# sheet.net
KiCad netlist of a schematic drawn in Altium Designer
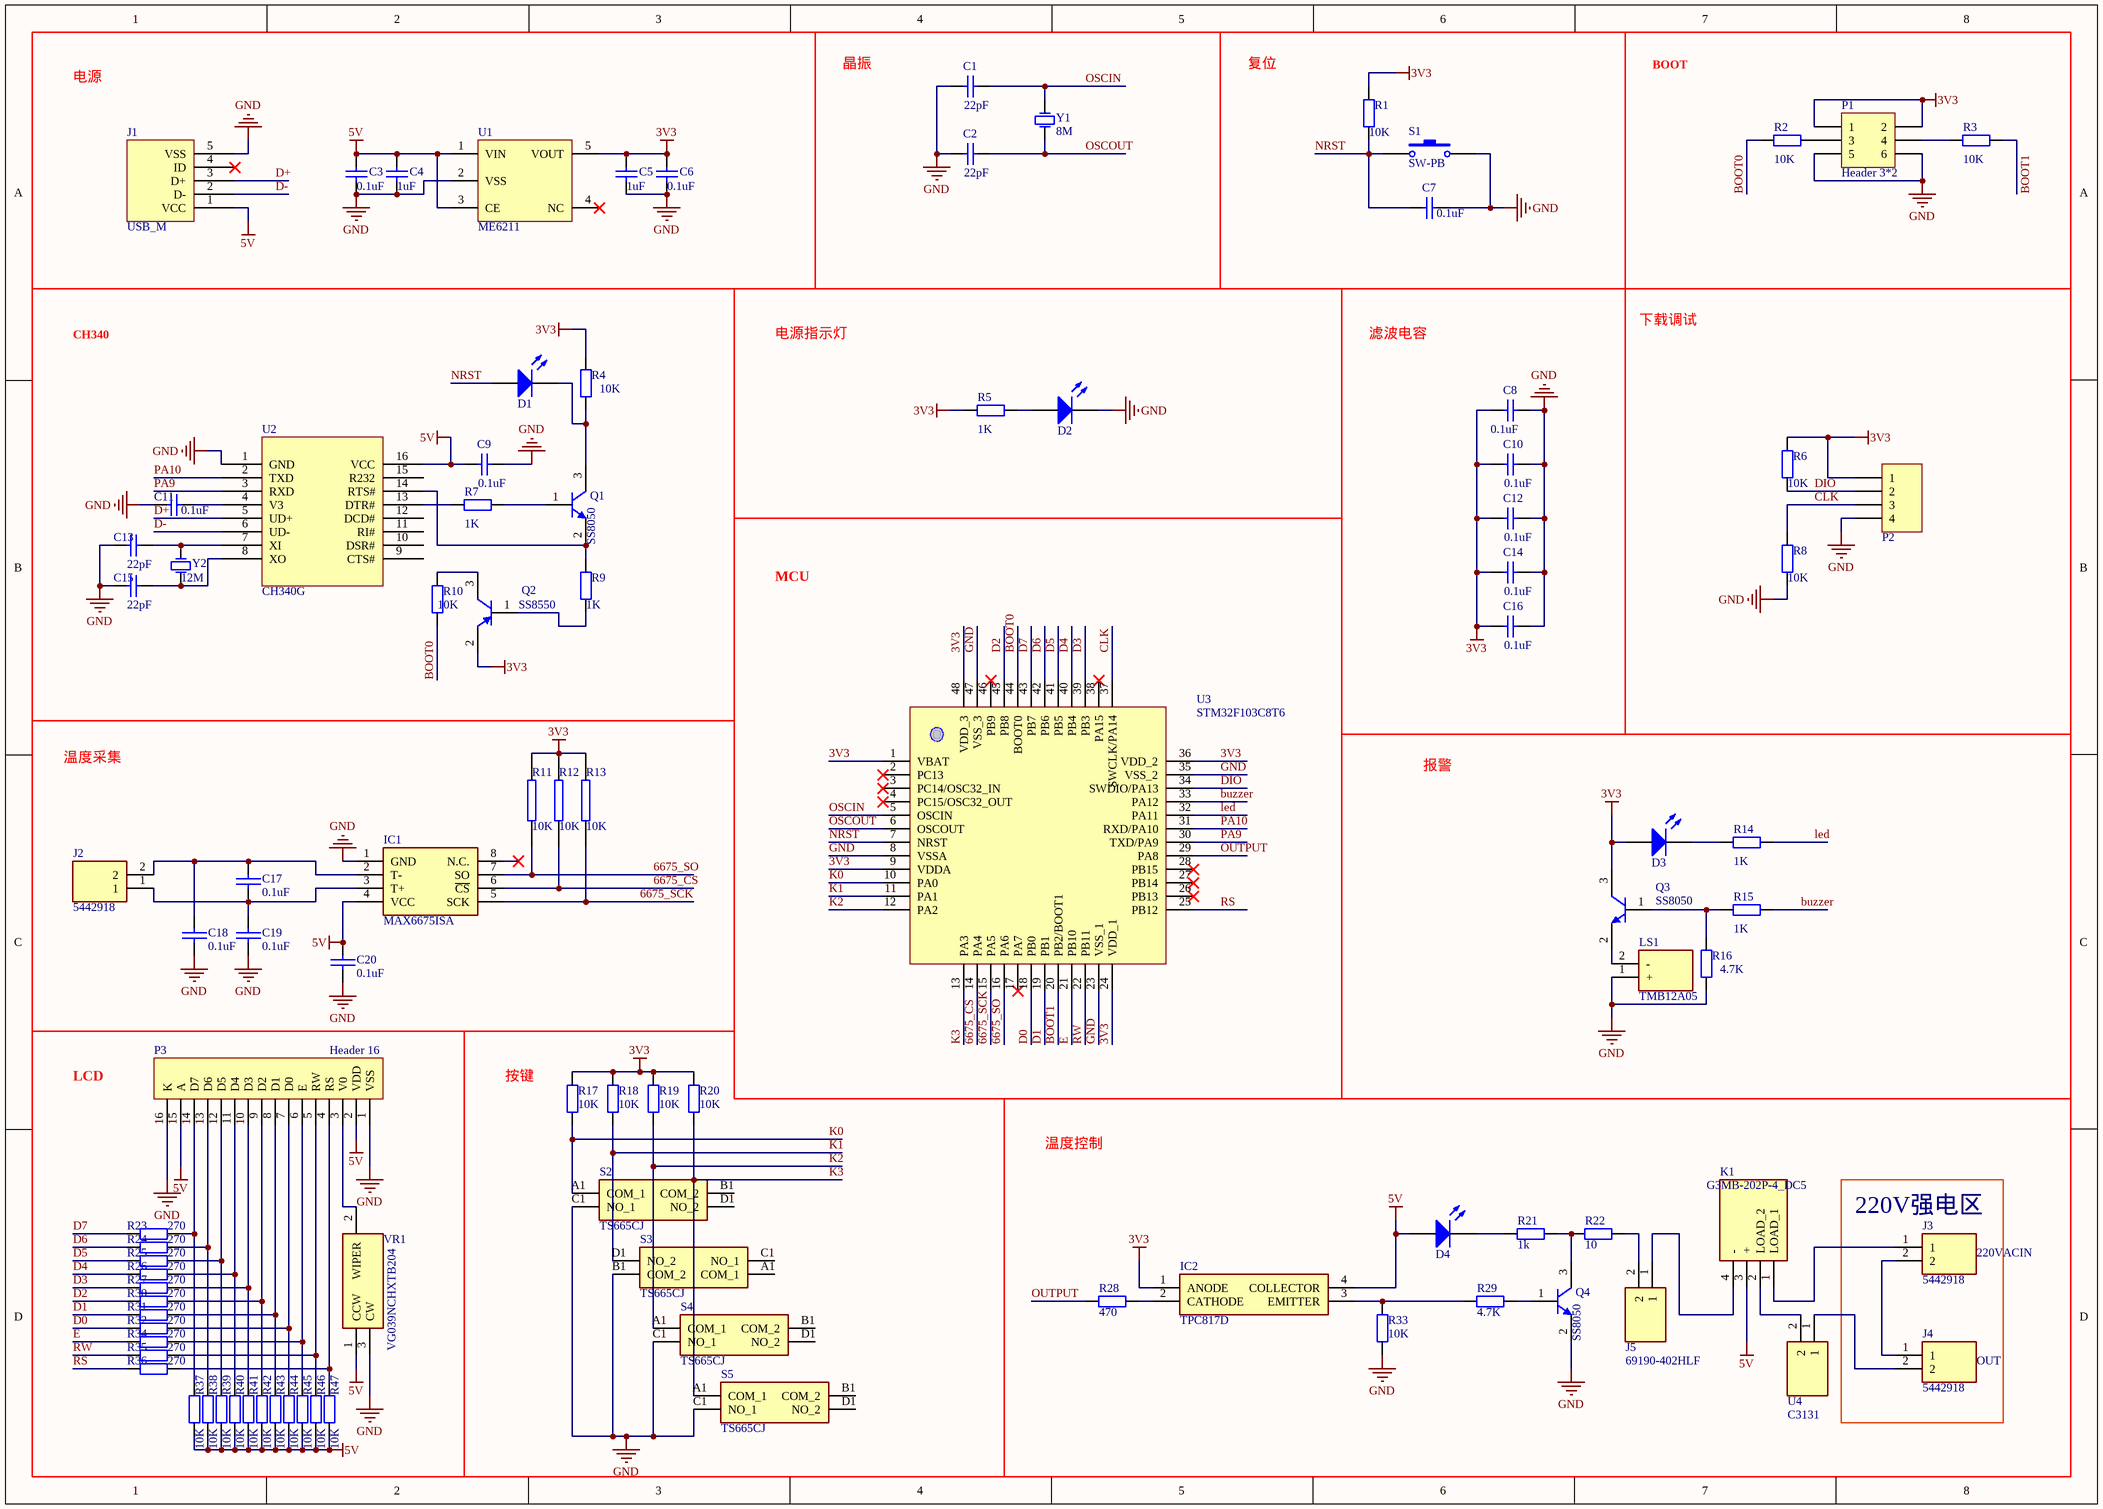
[diagram p0: sheet.SchDoc]

(export (version "E")
  (design (tool "Eeschema 10.0.6"))
  (components
    (comp (ref "C1")
      (value "22pF")
      (footprint "0603_C")
      (description "无极性电容")
      (fields (field (name "PUBLISHER") "Altium Limited"))
      (libsource (lib "stm32test") (part "Cap"))
    )
    (comp (ref "C2")
      (value "22pF")
      (footprint "0603_C")
      (description "无极性电容")
      (fields (field (name "PUBLISHER") "Altium Limited"))
      (libsource (lib "stm32test") (part "Cap"))
    )
    (comp (ref "C3")
      (value "0.1uF")
      (footprint "0603_C")
      (description "无极性电容")
      (fields (field (name "PUBLISHER") "Altium Limited"))
      (libsource (lib "stm32test") (part "Cap"))
    )
    (comp (ref "C4")
      (value "1uF")
      (footprint "0603_C")
      (description "无极性电容")
      (fields (field (name "PUBLISHER") "Altium Limited"))
      (libsource (lib "stm32test") (part "Cap"))
    )
    (comp (ref "C5")
      (value "1uF")
      (footprint "0603_C")
      (description "无极性电容")
      (fields (field (name "PUBLISHER") "Altium Limited"))
      (libsource (lib "stm32test") (part "Cap"))
    )
    (comp (ref "C6")
      (value "0.1uF")
      (footprint "0603_C")
      (description "无极性电容")
      (fields (field (name "PUBLISHER") "Altium Limited"))
      (libsource (lib "stm32test") (part "Cap"))
    )
    (comp (ref "C7")
      (value "0.1uF")
      (footprint "0603_C")
      (description "无极性电容")
      (fields (field (name "PUBLISHER") "Altium Limited"))
      (libsource (lib "stm32test") (part "Cap"))
    )
    (comp (ref "C8")
      (value "0.1uF")
      (footprint "0603_C")
      (description "无极性电容")
      (fields (field (name "PUBLISHER") "Altium Limited"))
      (libsource (lib "stm32test") (part "Cap"))
    )
    (comp (ref "C9")
      (value "0.1uF")
      (footprint "0603_C")
      (description "无极性电容")
      (fields (field (name "PUBLISHER") "Altium Limited"))
      (libsource (lib "stm32test") (part "Cap"))
    )
    (comp (ref "C10")
      (value "0.1uF")
      (footprint "0603_C")
      (description "无极性电容")
      (fields (field (name "PUBLISHER") "Altium Limited"))
      (libsource (lib "stm32test") (part "Cap"))
    )
    (comp (ref "C11")
      (value "0.1uF")
      (footprint "0603_C")
      (description "无极性电容")
      (fields (field (name "PUBLISHER") "Altium Limited"))
      (libsource (lib "stm32test") (part "Cap"))
    )
    (comp (ref "C12")
      (value "0.1uF")
      (footprint "0603_C")
      (description "无极性电容")
      (fields (field (name "PUBLISHER") "Altium Limited"))
      (libsource (lib "stm32test") (part "Cap"))
    )
    (comp (ref "C13")
      (value "22pF")
      (footprint "0603_C")
      (description "无极性电容")
      (fields (field (name "PUBLISHER") "Altium Limited"))
      (libsource (lib "stm32test") (part "Cap"))
    )
    (comp (ref "C14")
      (value "0.1uF")
      (footprint "0603_C")
      (description "无极性电容")
      (fields (field (name "PUBLISHER") "Altium Limited"))
      (libsource (lib "stm32test") (part "Cap"))
    )
    (comp (ref "C15")
      (value "22pF")
      (footprint "0603_C")
      (description "无极性电容")
      (fields (field (name "PUBLISHER") "Altium Limited"))
      (libsource (lib "stm32test") (part "Cap"))
    )
    (comp (ref "C16")
      (value "0.1uF")
      (footprint "0603_C")
      (description "无极性电容")
      (fields (field (name "PUBLISHER") "Altium Limited"))
      (libsource (lib "stm32test") (part "Cap"))
    )
    (comp (ref "C17")
      (value "0.1uF")
      (footprint "1206")
      (description "Capacitor")
      (libsource (lib "电容") (part "普通电容"))
    )
    (comp (ref "C18")
      (value "0.1uF")
      (footprint "1206")
      (description "Capacitor")
      (libsource (lib "电容") (part "普通电容"))
    )
    (comp (ref "C19")
      (value "0.1uF")
      (footprint "1206")
      (description "Capacitor")
      (libsource (lib "电容") (part "普通电容"))
    )
    (comp (ref "C20")
      (value "0.1uF")
      (footprint "1206")
      (description "Capacitor")
      (libsource (lib "电容") (part "普通电容"))
    )
    (comp (ref "D1")
      (value "LED0")
      (footprint "LED_0805_Blue")
      (description "发光二极管")
      (fields (field (name "PUBLISHER") "Altium Limited"))
      (libsource (lib "stm32test") (part "LED0"))
    )
    (comp (ref "D2")
      (value "LED0")
      (footprint "LED_0805_Blue")
      (description "发光二极管")
      (fields (field (name "PUBLISHER") "Altium Limited"))
      (libsource (lib "stm32test") (part "LED0"))
    )
    (comp (ref "D3")
      (value "LED0")
      (footprint "LED_0805_Blue")
      (description "发光二极管")
      (fields (field (name "PUBLISHER") "Altium Limited"))
      (libsource (lib "stm32test") (part "LED0"))
    )
    (comp (ref "D4")
      (value "LED0")
      (footprint "LED_0805_Blue")
      (description "发光二极管")
      (fields (field (name "PUBLISHER") "Altium Limited"))
      (libsource (lib "stm32test") (part "LED0"))
    )
    (comp (ref "IC1")
      (value "MAX6675ISA")
      (footprint "SamacSys:SOIC127P600X175-8N")
      (description "Integrated Circuit")
      (libsource (lib "SamacSys") (part "MAX6675ISA"))
    )
    (comp (ref "IC2")
      (value "TPC817D")
      (footprint "SamacSys:DIP810W50P254L460H368Q4N")
      (description "Integrated Circuit")
      (fields (field (name "MOUSER PART NUMBER") "821-TPC817D"))
      (libsource (lib "SamacSys") (part "TPC817D"))
    )
    (comp (ref "J1")
      (value "USB_M")
      (footprint "USB")
      (description "MicroUSB接口")
      (libsource (lib "stm32test") (part "USB_M"))
    )
    (comp (ref "J2")
      (value "5442918")
      (footprint "SamacSys:SHDR2W100P0X508_1X2_1016X1120X1820P")
      (description "Connector")
      (fields (field (name "MOUSER PART NUMBER") "651-5442918"))
      (libsource (lib "") (part "5442918_1"))
    )
    (comp (ref "J3")
      (value "5442918")
      (footprint "SamacSys:SHDR2W100P0X508_1X2_1016X1120X1820P")
      (description "Connector")
      (fields (field (name "MOUSER PART NUMBER") "651-5442918"))
      (libsource (lib "*") (part "5442918"))
    )
    (comp (ref "J4")
      (value "5442918")
      (footprint "SamacSys:SHDR2W100P0X508_1X2_1016X1120X1820P")
      (description "Connector")
      (fields (field (name "MOUSER PART NUMBER") "651-5442918"))
      (libsource (lib "*") (part "5442918"))
    )
    (comp (ref "J5")
      (value "69190-402HLF")
      (footprint "SamacSys:HDRV2W90P0X254_1X2_508X241X858P")
      (description "Connector")
      (fields
        (field (name "MOUSER PART NUMBER") "649-69190-402HLF")
        (field (name "RS PART NUMBER") "8632731")
      )
      (libsource (lib "*") (part "69190-402HLF"))
    )
    (comp (ref "K1")
      (value "G3MB-202P-4_DC5")
      (footprint "SamacSys:G3MB202P4DC5")
      (description "Relay or Contactor")
      (fields
        (field (name "MANUFACTURER_PART_NUMBER") "G3MB-202P-4 DC5")
        (field (name "MOUSER PART NUMBER") "653-G3MB-202P4DC5")
      )
      (libsource (lib "*") (part "G3MB-202P-4_DC5"))
    )
    (comp (ref "LS1")
      (value "TMB12A05")
      (footprint "SamacSys:TMB12A05")
      (description "Loudspeaker or Buzzer")
      (libsource (lib "*") (part "TMB12A05"))
    )
    (comp (ref "P1")
      (value "Header 3*2")
      (footprint "HDR3X2")
      (description "接插件")
      (libsource (lib "stm32test") (part "Header 3*2"))
    )
    (comp (ref "P2")
      (value "Header 4")
      (footprint "HDR4X1_A")
      (description "接插件")
      (fields (field (name "PUBLISHER") "Altium Limited"))
      (libsource (lib "stm32test") (part "Header 4"))
    )
    (comp (ref "P3")
      (value "Header 16")
      (footprint "HDR16X1_A")
      (description "Header16贴片")
      (fields (field (name "PUBLISHER") "Altium Limited"))
      (libsource (lib "stm32test") (part "Header 16"))
    )
    (comp (ref "Q1")
      (value "SS8050")
      (footprint "SOT-23")
      (description "NPN贴片三极管")
      (fields (field (name "PUBLISHER") "Altium Limited"))
      (libsource (lib "stm32test") (part "SS8050"))
    )
    (comp (ref "Q2")
      (value "SS8550")
      (footprint "SOT-23")
      (description "PNP贴片三极管")
      (fields (field (name "PUBLISHER") "Altium Limited"))
      (libsource (lib "stm32test") (part "SS8550"))
    )
    (comp (ref "Q3")
      (value "SS8050")
      (footprint "SOT-23")
      (description "NPN贴片三极管")
      (fields (field (name "PUBLISHER") "Altium Limited"))
      (libsource (lib "stm32test") (part "SS8050"))
    )
    (comp (ref "Q4")
      (value "SS8050")
      (footprint "SOT-23")
      (description "NPN贴片三极管")
      (fields (field (name "PUBLISHER") "Altium Limited"))
      (libsource (lib "stm32test") (part "SS8050"))
    )
    (comp (ref "R1")
      (value "10K")
      (footprint "0603_R")
      (description "贴片电阻")
      (fields (field (name "PUBLISHER") "Altium Limited"))
      (libsource (lib "stm32test") (part "Res1"))
    )
    (comp (ref "R2")
      (value "10K")
      (footprint "0603_R")
      (description "贴片电阻")
      (fields (field (name "PUBLISHER") "Altium Limited"))
      (libsource (lib "") (part "Res1_2"))
    )
    (comp (ref "R3")
      (value "10K")
      (footprint "0603_R")
      (description "贴片电阻")
      (fields (field (name "PUBLISHER") "Altium Limited"))
      (libsource (lib "") (part "Res1_2"))
    )
    (comp (ref "R4")
      (value "10K")
      (footprint "0603_R")
      (description "贴片电阻")
      (fields (field (name "PUBLISHER") "Altium Limited"))
      (libsource (lib "stm32test") (part "Res1"))
    )
    (comp (ref "R5")
      (value "1K")
      (footprint "0603_R")
      (description "贴片电阻")
      (fields (field (name "PUBLISHER") "Altium Limited"))
      (libsource (lib "") (part "Res1_2"))
    )
    (comp (ref "R6")
      (value "10K")
      (footprint "0603_R")
      (description "贴片电阻")
      (fields (field (name "PUBLISHER") "Altium Limited"))
      (libsource (lib "stm32test") (part "Res1"))
    )
    (comp (ref "R7")
      (value "1K")
      (footprint "0603_R")
      (description "贴片电阻")
      (fields (field (name "PUBLISHER") "Altium Limited"))
      (libsource (lib "") (part "Res1_2"))
    )
    (comp (ref "R8")
      (value "10K")
      (footprint "0603_R")
      (description "贴片电阻")
      (fields (field (name "PUBLISHER") "Altium Limited"))
      (libsource (lib "stm32test") (part "Res1"))
    )
    (comp (ref "R9")
      (value "1K")
      (footprint "0603_R")
      (description "贴片电阻")
      (fields (field (name "PUBLISHER") "Altium Limited"))
      (libsource (lib "stm32test") (part "Res1"))
    )
    (comp (ref "R10")
      (value "10K")
      (footprint "0603_R")
      (description "贴片电阻")
      (fields (field (name "PUBLISHER") "Altium Limited"))
      (libsource (lib "stm32test") (part "Res1"))
    )
    (comp (ref "R11") (value "10K") (footprint "1206") (libsource (lib "*") (part "RES2")))
    (comp (ref "R12") (value "10K") (footprint "1206") (libsource (lib "*") (part "RES2")))
    (comp (ref "R13") (value "10K") (footprint "1206") (libsource (lib "*") (part "RES2")))
    (comp (ref "R14")
      (value "1K")
      (footprint "0603_R")
      (description "贴片电阻")
      (fields (field (name "PUBLISHER") "Altium Limited"))
      (libsource (lib "") (part "Res1_2"))
    )
    (comp (ref "R15")
      (value "1K")
      (footprint "0603_R")
      (description "贴片电阻")
      (fields (field (name "PUBLISHER") "Altium Limited"))
      (libsource (lib "") (part "Res1_2"))
    )
    (comp (ref "R16")
      (value "4.7K")
      (footprint "0603_R")
      (description "贴片电阻")
      (fields (field (name "PUBLISHER") "Altium Limited"))
      (libsource (lib "stm32test") (part "Res1"))
    )
    (comp (ref "R17")
      (value "10K")
      (footprint "1206")
      (description "Resistor")
      (fields (field (name "PUBLISHER") "Altium Limited"))
      (libsource (lib "") (part "Res2_1"))
    )
    (comp (ref "R18")
      (value "10K")
      (footprint "1206")
      (description "Resistor")
      (fields (field (name "PUBLISHER") "Altium Limited"))
      (libsource (lib "") (part "Res2_1"))
    )
    (comp (ref "R19")
      (value "10K")
      (footprint "1206")
      (description "Resistor")
      (fields (field (name "PUBLISHER") "Altium Limited"))
      (libsource (lib "") (part "Res2_1"))
    )
    (comp (ref "R20")
      (value "10K")
      (footprint "1206")
      (description "Resistor")
      (fields (field (name "PUBLISHER") "Altium Limited"))
      (libsource (lib "") (part "Res2_1"))
    )
    (comp (ref "R21")
      (value "1k")
      (footprint "1206")
      (description "Resistor")
      (fields (field (name "PUBLISHER") "Altium Limited"))
      (libsource (lib "Miscellaneous Devices") (part "Res2"))
    )
    (comp (ref "R22")
      (value "10")
      (footprint "1206")
      (description "Resistor")
      (fields (field (name "PUBLISHER") "Altium Limited"))
      (libsource (lib "Miscellaneous Devices") (part "Res2"))
    )
    (comp (ref "R23")
      (value "270")
      (footprint "0603_R")
      (description "贴片电阻")
      (fields (field (name "PUBLISHER") "Altium Limited"))
      (libsource (lib "") (part "Res1_1"))
    )
    (comp (ref "R24")
      (value "270")
      (footprint "0603_R")
      (description "贴片电阻")
      (fields (field (name "PUBLISHER") "Altium Limited"))
      (libsource (lib "") (part "Res1_1"))
    )
    (comp (ref "R25")
      (value "270")
      (footprint "0603_R")
      (description "贴片电阻")
      (fields (field (name "PUBLISHER") "Altium Limited"))
      (libsource (lib "") (part "Res1_1"))
    )
    (comp (ref "R26")
      (value "270")
      (footprint "0603_R")
      (description "贴片电阻")
      (fields (field (name "PUBLISHER") "Altium Limited"))
      (libsource (lib "") (part "Res1_1"))
    )
    (comp (ref "R27")
      (value "270")
      (footprint "0603_R")
      (description "贴片电阻")
      (fields (field (name "PUBLISHER") "Altium Limited"))
      (libsource (lib "") (part "Res1_1"))
    )
    (comp (ref "R28")
      (value "470")
      (footprint "1206")
      (description "Resistor")
      (fields (field (name "PUBLISHER") "Altium Limited"))
      (libsource (lib "") (part "Res2_2"))
    )
    (comp (ref "R29")
      (value "4.7K")
      (footprint "1206")
      (description "Resistor")
      (fields (field (name "PUBLISHER") "Altium Limited"))
      (libsource (lib "") (part "Res2_2"))
    )
    (comp (ref "R30")
      (value "270")
      (footprint "0603_R")
      (description "贴片电阻")
      (fields (field (name "PUBLISHER") "Altium Limited"))
      (libsource (lib "") (part "Res1_1"))
    )
    (comp (ref "R31")
      (value "270")
      (footprint "0603_R")
      (description "贴片电阻")
      (fields (field (name "PUBLISHER") "Altium Limited"))
      (libsource (lib "") (part "Res1_1"))
    )
    (comp (ref "R32")
      (value "270")
      (footprint "0603_R")
      (description "贴片电阻")
      (fields (field (name "PUBLISHER") "Altium Limited"))
      (libsource (lib "") (part "Res1_1"))
    )
    (comp (ref "R33")
      (value "10K")
      (footprint "1206")
      (description "Resistor")
      (fields (field (name "PUBLISHER") "Altium Limited"))
      (libsource (lib "") (part "Res2_1"))
    )
    (comp (ref "R34")
      (value "270")
      (footprint "0603_R")
      (description "贴片电阻")
      (fields (field (name "PUBLISHER") "Altium Limited"))
      (libsource (lib "") (part "Res1_1"))
    )
    (comp (ref "R35")
      (value "270")
      (footprint "0603_R")
      (description "贴片电阻")
      (fields (field (name "PUBLISHER") "Altium Limited"))
      (libsource (lib "") (part "Res1_1"))
    )
    (comp (ref "R36")
      (value "270")
      (footprint "0603_R")
      (description "贴片电阻")
      (fields (field (name "PUBLISHER") "Altium Limited"))
      (libsource (lib "") (part "Res1_1"))
    )
    (comp (ref "R37")
      (value "10K")
      (footprint "0603_R")
      (description "贴片电阻")
      (fields (field (name "PUBLISHER") "Altium Limited"))
      (libsource (lib "stm32test") (part "Res1"))
    )
    (comp (ref "R38")
      (value "10K")
      (footprint "0603_R")
      (description "贴片电阻")
      (fields (field (name "PUBLISHER") "Altium Limited"))
      (libsource (lib "stm32test") (part "Res1"))
    )
    (comp (ref "R39")
      (value "10K")
      (footprint "0603_R")
      (description "贴片电阻")
      (fields (field (name "PUBLISHER") "Altium Limited"))
      (libsource (lib "stm32test") (part "Res1"))
    )
    (comp (ref "R40")
      (value "10K")
      (footprint "0603_R")
      (description "贴片电阻")
      (fields (field (name "PUBLISHER") "Altium Limited"))
      (libsource (lib "stm32test") (part "Res1"))
    )
    (comp (ref "R41")
      (value "10K")
      (footprint "0603_R")
      (description "贴片电阻")
      (fields (field (name "PUBLISHER") "Altium Limited"))
      (libsource (lib "stm32test") (part "Res1"))
    )
    (comp (ref "R42")
      (value "10K")
      (footprint "0603_R")
      (description "贴片电阻")
      (fields (field (name "PUBLISHER") "Altium Limited"))
      (libsource (lib "stm32test") (part "Res1"))
    )
    (comp (ref "R43")
      (value "10K")
      (footprint "0603_R")
      (description "贴片电阻")
      (fields (field (name "PUBLISHER") "Altium Limited"))
      (libsource (lib "stm32test") (part "Res1"))
    )
    (comp (ref "R44")
      (value "10K")
      (footprint "0603_R")
      (description "贴片电阻")
      (fields (field (name "PUBLISHER") "Altium Limited"))
      (libsource (lib "stm32test") (part "Res1"))
    )
    (comp (ref "R45")
      (value "10K")
      (footprint "0603_R")
      (description "贴片电阻")
      (fields (field (name "PUBLISHER") "Altium Limited"))
      (libsource (lib "stm32test") (part "Res1"))
    )
    (comp (ref "R46")
      (value "10K")
      (footprint "0603_R")
      (description "贴片电阻")
      (fields (field (name "PUBLISHER") "Altium Limited"))
      (libsource (lib "stm32test") (part "Res1"))
    )
    (comp (ref "R47")
      (value "10K")
      (footprint "0603_R")
      (description "贴片电阻")
      (fields (field (name "PUBLISHER") "Altium Limited"))
      (libsource (lib "stm32test") (part "Res1"))
    )
    (comp (ref "S1")
      (value "SW-PB")
      (footprint "SW_PB2_A1")
      (description "微动开关")
      (fields (field (name "PUBLISHER") "Altium Limited"))
      (libsource (lib "stm32test") (part "SW-PB"))
    )
    (comp (ref "S2")
      (value "TS665CJ")
      (footprint "SamacSys:TS665CJ")
      (description "Switch")
      (libsource (lib "*") (part "TS665CJ"))
    )
    (comp (ref "S3")
      (value "TS665CJ")
      (footprint "SamacSys:TS665CJ")
      (description "Switch")
      (libsource (lib "") (part "TS665CJ_1"))
    )
    (comp (ref "S4")
      (value "TS665CJ")
      (footprint "SamacSys:TS665CJ")
      (description "Switch")
      (libsource (lib "*") (part "TS665CJ"))
    )
    (comp (ref "S5")
      (value "TS665CJ")
      (footprint "SamacSys:TS665CJ")
      (description "Switch")
      (libsource (lib "*") (part "TS665CJ"))
    )
    (comp (ref "U1") (value "ME6211") (footprint "SOT23-5") (libsource (lib "stm32test") (part "ME6211")))
    (comp (ref "U2")
      (value "CH340G")
      (footprint "SOP-16")
      (description "串口芯片")
      (libsource (lib "stm32test") (part "CH340G"))
    )
    (comp (ref "U3")
      (value "STM32F103C8T6")
      (footprint "LQFP-48_M")
      (description "STM32单片机48引脚")
      (libsource (lib "stm32test") (part "STM32F103C8T6"))
    )
    (comp (ref "U4")
      (value "C3131")
      (footprint "SamacSys:C3131")
      (description "Undefined or Miscellaneous")
      (libsource (lib "*") (part "C3131"))
    )
    (comp (ref "VR1")
      (value "VG039NCHXTB204")
      (footprint "SamacSys:VG039NCHXTB204")
      (description "Variable Resistor")
      (libsource (lib "*") (part "VG039NCHXTB204"))
    )
    (comp (ref "Y1")
      (value "8M")
      (footprint "5032")
      (description "晶振")
      (fields (field (name "PUBLISHER") "Altium Limited"))
      (libsource (lib "stm32test") (part "XTAL"))
    )
    (comp (ref "Y2")
      (value "12M")
      (footprint "5032")
      (description "晶振")
      (fields (field (name "PUBLISHER") "Altium Limited"))
      (libsource (lib "stm32test") (part "XTAL"))
    )
  )
  (nets
    (net (code "1") (name "/6675_CS") (class "Default")
      (node (ref "IC1") (pin "6") (pinfunction "~{CS}_6") (pintype "passive"))
      (node (ref "R12") (pin "1") (pinfunction "1_1") (pintype "passive"))
      (node (ref "U3") (pin "14") (pinfunction "PA4_14") (pintype "passive"))
    )
    (net (code "2") (name "/6675_SCK") (class "Default")
      (node (ref "IC1") (pin "5") (pinfunction "SCK_5") (pintype "passive"))
      (node (ref "R13") (pin "1") (pinfunction "1_1") (pintype "passive"))
      (node (ref "U3") (pin "15") (pinfunction "PA5_15") (pintype "passive"))
    )
    (net (code "3") (name "/6675_SO") (class "Default")
      (node (ref "IC1") (pin "7") (pinfunction "SO_7") (pintype "passive"))
      (node (ref "R11") (pin "1") (pinfunction "1_1") (pintype "passive"))
      (node (ref "U3") (pin "16") (pinfunction "PA6_16") (pintype "passive"))
    )
    (net (code "5") (name "/BOOT0") (class "Default")
      (node (ref "R10") (pin "1") (pinfunction "1_1") (pintype "passive"))
      (node (ref "R2") (pin "1") (pinfunction "1_1") (pintype "passive"))
      (node (ref "U3") (pin "44") (pinfunction "BOOT0_44") (pintype "passive"))
    )
    (net (code "6") (name "/BOOT1") (class "Default")
      (node (ref "R3") (pin "2") (pinfunction "2_2") (pintype "passive"))
      (node (ref "U3") (pin "20") (pinfunction "PB2/BOOT1_20") (pintype "passive"))
    )
    (net (code "7") (name "/CLK") (class "Default")
      (node (ref "P2") (pin "3") (pinfunction "3_3") (pintype "passive"))
      (node (ref "R8") (pin "2") (pinfunction "2_2") (pintype "passive"))
      (node (ref "U3") (pin "37") (pinfunction "SWCLK/PA14_37") (pintype "passive"))
    )
    (net (code "8") (name "/D+") (class "Default")
      (node (ref "J1") (pin "3") (pinfunction "D+_3") (pintype "passive"))
      (node (ref "U2") (pin "5") (pinfunction "UD+_5") (pintype "passive"))
    )
    (net (code "9") (name "/D-") (class "Default")
      (node (ref "J1") (pin "2") (pinfunction "D-_2") (pintype "passive"))
      (node (ref "U2") (pin "6") (pinfunction "UD-_6") (pintype "passive"))
    )
    (net (code "10") (name "/D0") (class "Default")
      (node (ref "R32") (pin "2") (pinfunction "2_2") (pintype "passive"))
      (node (ref "U3") (pin "18") (pinfunction "PB0_18") (pintype "passive"))
    )
    (net (code "11") (name "/D1") (class "Default")
      (node (ref "R31") (pin "2") (pinfunction "2_2") (pintype "passive"))
      (node (ref "U3") (pin "19") (pinfunction "PB1_19") (pintype "passive"))
    )
    (net (code "12") (name "/D2") (class "Default")
      (node (ref "R30") (pin "2") (pinfunction "2_2") (pintype "passive"))
      (node (ref "U3") (pin "45") (pinfunction "PB8_45") (pintype "passive"))
    )
    (net (code "13") (name "/D3") (class "Default")
      (node (ref "R27") (pin "2") (pinfunction "2_2") (pintype "passive"))
      (node (ref "U3") (pin "39") (pinfunction "PB3_39") (pintype "passive"))
    )
    (net (code "14") (name "/D4") (class "Default")
      (node (ref "R26") (pin "2") (pinfunction "2_2") (pintype "passive"))
      (node (ref "U3") (pin "40") (pinfunction "PB4_40") (pintype "passive"))
    )
    (net (code "15") (name "/D5") (class "Default")
      (node (ref "R25") (pin "2") (pinfunction "2_2") (pintype "passive"))
      (node (ref "U3") (pin "41") (pinfunction "PB5_41") (pintype "passive"))
    )
    (net (code "16") (name "/D6") (class "Default")
      (node (ref "R24") (pin "2") (pinfunction "2_2") (pintype "passive"))
      (node (ref "U3") (pin "42") (pinfunction "PB6_42") (pintype "passive"))
    )
    (net (code "17") (name "/D7") (class "Default")
      (node (ref "R23") (pin "2") (pinfunction "2_2") (pintype "passive"))
      (node (ref "U3") (pin "43") (pinfunction "PB7_43") (pintype "passive"))
    )
    (net (code "18") (name "/DIO") (class "Default")
      (node (ref "P2") (pin "2") (pinfunction "2_2") (pintype "passive"))
      (node (ref "R6") (pin "1") (pinfunction "1_1") (pintype "passive"))
      (node (ref "U3") (pin "34") (pinfunction "SWDIO/PA13_34") (pintype "passive"))
    )
    (net (code "19") (name "/E") (class "Default")
      (node (ref "R34") (pin "2") (pinfunction "2_2") (pintype "passive"))
      (node (ref "U3") (pin "21") (pinfunction "PB10_21") (pintype "passive"))
    )
    (net (code "20") (name "/K0") (class "Default")
      (node (ref "R17") (pin "1") (pinfunction "1_1") (pintype "passive"))
      (node (ref "S2") (pin "A1") (pinfunction "COM_1_A1") (pintype "passive"))
      (node (ref "U3") (pin "10") (pinfunction "PA0_10") (pintype "passive"))
    )
    (net (code "21") (name "/K1") (class "Default")
      (node (ref "R18") (pin "1") (pinfunction "1_1") (pintype "passive"))
      (node (ref "S3") (pin "D1") (pinfunction "NO_2_D1") (pintype "passive"))
      (node (ref "U3") (pin "11") (pinfunction "PA1_11") (pintype "passive"))
    )
    (net (code "22") (name "/K2") (class "Default")
      (node (ref "R19") (pin "1") (pinfunction "1_1") (pintype "passive"))
      (node (ref "S4") (pin "A1") (pinfunction "COM_1_A1") (pintype "passive"))
      (node (ref "U3") (pin "12") (pinfunction "PA2_12") (pintype "passive"))
    )
    (net (code "23") (name "/K3") (class "Default")
      (node (ref "R20") (pin "1") (pinfunction "1_1") (pintype "passive"))
      (node (ref "S5") (pin "A1") (pinfunction "COM_1_A1") (pintype "passive"))
      (node (ref "U3") (pin "13") (pinfunction "PA3_13") (pintype "passive"))
    )
    (net (code "24") (name "/NRST") (class "Default")
      (node (ref "C7") (pin "1") (pinfunction "1_1") (pintype "passive"))
      (node (ref "D1") (pin "1") (pinfunction "A_1") (pintype "passive"))
      (node (ref "R1") (pin "1") (pinfunction "1_1") (pintype "passive"))
      (node (ref "S1") (pin "1") (pinfunction "1_1") (pintype "passive"))
      (node (ref "U3") (pin "7") (pinfunction "NRST_7") (pintype "passive"))
    )
    (net (code "25") (name "/OSCIN") (class "Default")
      (node (ref "C1") (pin "1") (pinfunction "1_1") (pintype "passive"))
      (node (ref "U3") (pin "5") (pinfunction "OSCIN_5") (pintype "passive"))
      (node (ref "Y1") (pin "1") (pinfunction "OSC1_1") (pintype "passive"))
    )
    (net (code "26") (name "/OSCOUT") (class "Default")
      (node (ref "C2") (pin "1") (pinfunction "1_1") (pintype "passive"))
      (node (ref "U3") (pin "6") (pinfunction "OSCOUT_6") (pintype "passive"))
      (node (ref "Y1") (pin "2") (pinfunction "OSC2_2") (pintype "passive"))
    )
    (net (code "27") (name "/OUTPUT") (class "Default")
      (node (ref "R28") (pin "2") (pinfunction "2_2") (pintype "passive"))
      (node (ref "U3") (pin "29") (pinfunction "PA8_29") (pintype "passive"))
    )
    (net (code "28") (name "/PA9") (class "Default")
      (node (ref "U2") (pin "3") (pinfunction "RXD_3") (pintype "passive"))
      (node (ref "U3") (pin "30") (pinfunction "TXD/PA9_30") (pintype "passive"))
    )
    (net (code "29") (name "/PA10") (class "Default")
      (node (ref "U2") (pin "2") (pinfunction "TXD_2") (pintype "passive"))
      (node (ref "U3") (pin "31") (pinfunction "RXD/PA10_31") (pintype "passive"))
    )
    (net (code "30") (name "/RS") (class "Default")
      (node (ref "R36") (pin "2") (pinfunction "2_2") (pintype "passive"))
      (node (ref "U3") (pin "25") (pinfunction "PB12_25") (pintype "passive"))
    )
    (net (code "31") (name "/RW") (class "Default")
      (node (ref "R35") (pin "2") (pinfunction "2_2") (pintype "passive"))
      (node (ref "U3") (pin "22") (pinfunction "PB11_22") (pintype "passive"))
    )
    (net (code "32") (name "/buzzer") (class "Default")
      (node (ref "R15") (pin "2") (pinfunction "2_2") (pintype "passive"))
      (node (ref "U3") (pin "33") (pinfunction "PA12_33") (pintype "passive"))
    )
    (net (code "33") (name "/led") (class "Default")
      (node (ref "R14") (pin "2") (pinfunction "2_2") (pintype "passive"))
      (node (ref "U3") (pin "32") (pinfunction "PA11_32") (pintype "passive"))
    )
    (net (code "34") (name "3V3") (class "Default")
      (node (ref "C10") (pin "2") (pinfunction "2_2") (pintype "passive"))
      (node (ref "C12") (pin "2") (pinfunction "2_2") (pintype "passive"))
      (node (ref "C14") (pin "2") (pinfunction "2_2") (pintype "passive"))
      (node (ref "C16") (pin "2") (pinfunction "2_2") (pintype "passive"))
      (node (ref "C5") (pin "2") (pinfunction "2_2") (pintype "passive"))
      (node (ref "C6") (pin "2") (pinfunction "2_2") (pintype "passive"))
      (node (ref "C8") (pin "2") (pinfunction "2_2") (pintype "passive"))
      (node (ref "D3") (pin "1") (pinfunction "A_1") (pintype "passive"))
      (node (ref "IC2") (pin "1") (pinfunction "ANODE_1") (pintype "passive"))
      (node (ref "P1") (pin "1") (pinfunction "1_1") (pintype "passive"))
      (node (ref "P1") (pin "2") (pinfunction "2_2") (pintype "passive"))
      (node (ref "P2") (pin "1") (pinfunction "1_1") (pintype "passive"))
      (node (ref "Q2") (pin "2") (pinfunction "E_2") (pintype "passive"))
      (node (ref "Q3") (pin "3") (pinfunction "C_3") (pintype "passive"))
      (node (ref "R1") (pin "2") (pinfunction "2_2") (pintype "passive"))
      (node (ref "R11") (pin "2") (pinfunction "2_2") (pintype "passive"))
      (node (ref "R12") (pin "2") (pinfunction "2_2") (pintype "passive"))
      (node (ref "R13") (pin "2") (pinfunction "2_2") (pintype "passive"))
      (node (ref "R17") (pin "2") (pinfunction "2_2") (pintype "passive"))
      (node (ref "R18") (pin "2") (pinfunction "2_2") (pintype "passive"))
      (node (ref "R19") (pin "2") (pinfunction "2_2") (pintype "passive"))
      (node (ref "R20") (pin "2") (pinfunction "2_2") (pintype "passive"))
      (node (ref "R4") (pin "2") (pinfunction "2_2") (pintype "passive"))
      (node (ref "R5") (pin "1") (pinfunction "1_1") (pintype "passive"))
      (node (ref "R6") (pin "2") (pinfunction "2_2") (pintype "passive"))
      (node (ref "U1") (pin "5") (pinfunction "VOUT_5") (pintype "passive"))
      (node (ref "U3") (pin "1") (pinfunction "VBAT_1") (pintype "passive"))
      (node (ref "U3") (pin "24") (pinfunction "VDD_1_24") (pintype "passive"))
      (node (ref "U3") (pin "36") (pinfunction "VDD_2_36") (pintype "passive"))
      (node (ref "U3") (pin "48") (pinfunction "VDD_3_48") (pintype "passive"))
      (node (ref "U3") (pin "9") (pinfunction "VDDA_9") (pintype "passive"))
    )
    (net (code "35") (name "5V") (class "Default")
      (node (ref "C20") (pin "1") (pinfunction "1_1") (pintype "passive"))
      (node (ref "C3") (pin "2") (pinfunction "2_2") (pintype "passive"))
      (node (ref "C4") (pin "2") (pinfunction "2_2") (pintype "passive"))
      (node (ref "C9") (pin "1") (pinfunction "1_1") (pintype "passive"))
      (node (ref "D4") (pin "1") (pinfunction "A_1") (pintype "passive"))
      (node (ref "IC1") (pin "4") (pinfunction "VCC_4") (pintype "passive"))
      (node (ref "IC2") (pin "4") (pinfunction "COLLECTOR_4") (pintype "passive"))
      (node (ref "J1") (pin "1") (pinfunction "VCC_1") (pintype "passive"))
      (node (ref "K1") (pin "3") (pinfunction "+_3") (pintype "passive"))
      (node (ref "P3") (pin "15") (pinfunction "A_15") (pintype "passive"))
      (node (ref "P3") (pin "2") (pinfunction "VDD_2") (pintype "passive"))
      (node (ref "R37") (pin "1") (pinfunction "1_1") (pintype "passive"))
      (node (ref "R38") (pin "1") (pinfunction "1_1") (pintype "passive"))
      (node (ref "R39") (pin "1") (pinfunction "1_1") (pintype "passive"))
      (node (ref "R40") (pin "1") (pinfunction "1_1") (pintype "passive"))
      (node (ref "R41") (pin "1") (pinfunction "1_1") (pintype "passive"))
      (node (ref "R42") (pin "1") (pinfunction "1_1") (pintype "passive"))
      (node (ref "R43") (pin "1") (pinfunction "1_1") (pintype "passive"))
      (node (ref "R44") (pin "1") (pinfunction "1_1") (pintype "passive"))
      (node (ref "R45") (pin "1") (pinfunction "1_1") (pintype "passive"))
      (node (ref "R46") (pin "1") (pinfunction "1_1") (pintype "passive"))
      (node (ref "R47") (pin "1") (pinfunction "1_1") (pintype "passive"))
      (node (ref "U1") (pin "1") (pinfunction "VIN_1") (pintype "passive"))
      (node (ref "U1") (pin "3") (pinfunction "CE_3") (pintype "passive"))
      (node (ref "U2") (pin "16") (pinfunction "VCC_16") (pintype "power_in"))
      (node (ref "VR1") (pin "1") (pinfunction "CCW_1") (pintype "passive"))
    )
    (net (code "36") (name "GND") (class "Default")
      (node (ref "C1") (pin "2") (pinfunction "2_2") (pintype "passive"))
      (node (ref "C10") (pin "1") (pinfunction "1_1") (pintype "passive"))
      (node (ref "C11") (pin "1") (pinfunction "1_1") (pintype "passive"))
      (node (ref "C12") (pin "1") (pinfunction "1_1") (pintype "passive"))
      (node (ref "C13") (pin "2") (pinfunction "2_2") (pintype "passive"))
      (node (ref "C14") (pin "1") (pinfunction "1_1") (pintype "passive"))
      (node (ref "C15") (pin "2") (pinfunction "2_2") (pintype "passive"))
      (node (ref "C16") (pin "1") (pinfunction "1_1") (pintype "passive"))
      (node (ref "C18") (pin "2") (pinfunction "2_2") (pintype "passive"))
      (node (ref "C19") (pin "2") (pinfunction "2_2") (pintype "passive"))
      (node (ref "C2") (pin "2") (pinfunction "2_2") (pintype "passive"))
      (node (ref "C20") (pin "2") (pinfunction "2_2") (pintype "passive"))
      (node (ref "C3") (pin "1") (pinfunction "1_1") (pintype "passive"))
      (node (ref "C4") (pin "1") (pinfunction "1_1") (pintype "passive"))
      (node (ref "C5") (pin "1") (pinfunction "1_1") (pintype "passive"))
      (node (ref "C6") (pin "1") (pinfunction "1_1") (pintype "passive"))
      (node (ref "C7") (pin "2") (pinfunction "2_2") (pintype "passive"))
      (node (ref "C8") (pin "1") (pinfunction "1_1") (pintype "passive"))
      (node (ref "C9") (pin "2") (pinfunction "2_2") (pintype "passive"))
      (node (ref "D2") (pin "2") (pinfunction "K_2") (pintype "passive"))
      (node (ref "IC1") (pin "1") (pinfunction "GND_1") (pintype "passive"))
      (node (ref "J1") (pin "5") (pinfunction "VSS_5") (pintype "passive"))
      (node (ref "LS1") (pin "1") (pinfunction "+_1") (pintype "passive"))
      (node (ref "P1") (pin "5") (pinfunction "5_5") (pintype "passive"))
      (node (ref "P1") (pin "6") (pinfunction "6_6") (pintype "passive"))
      (node (ref "P2") (pin "4") (pinfunction "4_4") (pintype "passive"))
      (node (ref "P3") (pin "1") (pinfunction "VSS_1") (pintype "passive"))
      (node (ref "P3") (pin "16") (pinfunction "K_16") (pintype "passive"))
      (node (ref "Q4") (pin "2") (pinfunction "E_2") (pintype "passive"))
      (node (ref "R16") (pin "1") (pinfunction "1_1") (pintype "passive"))
      (node (ref "R33") (pin "1") (pinfunction "1_1") (pintype "passive"))
      (node (ref "R8") (pin "1") (pinfunction "1_1") (pintype "passive"))
      (node (ref "S1") (pin "2") (pinfunction "2_2") (pintype "passive"))
      (node (ref "S2") (pin "C1") (pinfunction "NO_1_C1") (pintype "passive"))
      (node (ref "S3") (pin "B1") (pinfunction "COM_2_B1") (pintype "passive"))
      (node (ref "S4") (pin "C1") (pinfunction "NO_1_C1") (pintype "passive"))
      (node (ref "S5") (pin "C1") (pinfunction "NO_1_C1") (pintype "passive"))
      (node (ref "U1") (pin "2") (pinfunction "VSS_2") (pintype "passive"))
      (node (ref "U2") (pin "1") (pinfunction "GND_1") (pintype "power_in"))
      (node (ref "U3") (pin "23") (pinfunction "VSS_1_23") (pintype "passive"))
      (node (ref "U3") (pin "35") (pinfunction "VSS_2_35") (pintype "passive"))
      (node (ref "U3") (pin "47") (pinfunction "VSS_3_47") (pintype "passive"))
      (node (ref "U3") (pin "8") (pinfunction "VSSA_8") (pintype "passive"))
      (node (ref "VR1") (pin "3") (pinfunction "CW_3") (pintype "passive"))
    )
    (net (code "37") (name "Net-(D1-K)") (class "Default")
      (node (ref "D1") (pin "2") (pinfunction "K_2") (pintype "passive"))
      (node (ref "Q1") (pin "3") (pinfunction "C_3") (pintype "passive"))
      (node (ref "R4") (pin "1") (pinfunction "1_1") (pintype "passive"))
    )
    (net (code "38") (name "Net-(D2-A)") (class "Default")
      (node (ref "D2") (pin "1") (pinfunction "A_1") (pintype "passive"))
      (node (ref "R5") (pin "2") (pinfunction "2_2") (pintype "passive"))
    )
    (net (code "39") (name "Net-(D3-K)") (class "Default")
      (node (ref "D3") (pin "2") (pinfunction "K_2") (pintype "passive"))
      (node (ref "R14") (pin "1") (pinfunction "1_1") (pintype "passive"))
    )
    (net (code "40") (name "Net-(D4-K)") (class "Default")
      (node (ref "D4") (pin "2") (pinfunction "K_2") (pintype "passive"))
      (node (ref "R21") (pin "2") (pinfunction "2_2") (pintype "passive"))
    )
    (net (code "41") (name "Net-(IC1-T+)") (class "Default")
      (node (ref "C17") (pin "2") (pinfunction "2_2") (pintype "passive"))
      (node (ref "C19") (pin "1") (pinfunction "1_1") (pintype "passive"))
      (node (ref "IC1") (pin "3") (pinfunction "T+_3") (pintype "passive"))
      (node (ref "J2") (pin "1") (pinfunction "1_1") (pintype "passive"))
    )
    (net (code "42") (name "Net-(IC1-T-)") (class "Default")
      (node (ref "C17") (pin "1") (pinfunction "1_1") (pintype "passive"))
      (node (ref "C18") (pin "1") (pinfunction "1_1") (pintype "passive"))
      (node (ref "IC1") (pin "2") (pinfunction "T-_2") (pintype "passive"))
      (node (ref "J2") (pin "2") (pinfunction "2_2") (pintype "passive"))
    )
    (net (code "43") (name "Net-(IC2-CATHODE)") (class "Default")
      (node (ref "IC2") (pin "2") (pinfunction "CATHODE_2") (pintype "passive"))
      (node (ref "R28") (pin "1") (pinfunction "1_1") (pintype "passive"))
    )
    (net (code "44") (name "Net-(IC2-EMITTER)") (class "Default")
      (node (ref "IC2") (pin "3") (pinfunction "EMITTER_3") (pintype "passive"))
      (node (ref "R29") (pin "2") (pinfunction "2_2") (pintype "passive"))
      (node (ref "R33") (pin "2") (pinfunction "2_2") (pintype "passive"))
    )
    (net (code "45") (name "Net-(J3-Pad2)") (class "Default")
      (node (ref "J3") (pin "2") (pinfunction "2_2") (pintype "passive"))
      (node (ref "J4") (pin "1") (pinfunction "1_1") (pintype "passive"))
    )
    (net (code "46") (name "Net-(J4-Pad2)") (class "Default")
      (node (ref "J4") (pin "2") (pinfunction "2_2") (pintype "passive"))
      (node (ref "U4") (pin "1") (pinfunction "1_1") (pintype "passive"))
    )
    (net (code "47") (name "Net-(J5-Pad2)") (class "Default")
      (node (ref "J5") (pin "2") (pinfunction "2_2") (pintype "passive"))
      (node (ref "R22") (pin "1") (pinfunction "1_1") (pintype "passive"))
    )
    (net (code "48") (name "Net-(K1--)") (class "Default")
      (node (ref "J5") (pin "1") (pinfunction "1_1") (pintype "passive"))
      (node (ref "K1") (pin "4") (pinfunction "-_4") (pintype "passive"))
    )
    (net (code "49") (name "Net-(K1-LOAD_1)") (class "Default")
      (node (ref "J3") (pin "1") (pinfunction "1_1") (pintype "passive"))
      (node (ref "K1") (pin "1") (pinfunction "LOAD_1_1") (pintype "passive"))
    )
    (net (code "50") (name "Net-(K1-LOAD_2)") (class "Default")
      (node (ref "K1") (pin "2") (pinfunction "LOAD_2_2") (pintype "passive"))
      (node (ref "U4") (pin "2") (pinfunction "2_2") (pintype "passive"))
    )
    (net (code "51") (name "Net-(LS1--)") (class "Default")
      (node (ref "LS1") (pin "2") (pinfunction "-_2") (pintype "passive"))
      (node (ref "Q3") (pin "2") (pinfunction "E_2") (pintype "passive"))
    )
    (net (code "52") (name "Net-(P1-Pad3)") (class "Default")
      (node (ref "P1") (pin "3") (pinfunction "3_3") (pintype "passive"))
      (node (ref "R2") (pin "2") (pinfunction "2_2") (pintype "passive"))
    )
    (net (code "53") (name "Net-(P1-Pad4)") (class "Default")
      (node (ref "P1") (pin "4") (pinfunction "4_4") (pintype "passive"))
      (node (ref "R3") (pin "1") (pinfunction "1_1") (pintype "passive"))
    )
    (net (code "54") (name "Net-(P3-D0)") (class "Default")
      (node (ref "P3") (pin "7") (pinfunction "D0_7") (pintype "passive"))
      (node (ref "R32") (pin "1") (pinfunction "1_1") (pintype "passive"))
      (node (ref "R44") (pin "2") (pinfunction "2_2") (pintype "passive"))
    )
    (net (code "55") (name "Net-(P3-D1)") (class "Default")
      (node (ref "P3") (pin "8") (pinfunction "D1_8") (pintype "passive"))
      (node (ref "R31") (pin "1") (pinfunction "1_1") (pintype "passive"))
      (node (ref "R43") (pin "2") (pinfunction "2_2") (pintype "passive"))
    )
    (net (code "56") (name "Net-(P3-D2)") (class "Default")
      (node (ref "P3") (pin "9") (pinfunction "D2_9") (pintype "passive"))
      (node (ref "R30") (pin "1") (pinfunction "1_1") (pintype "passive"))
      (node (ref "R42") (pin "2") (pinfunction "2_2") (pintype "passive"))
    )
    (net (code "57") (name "Net-(P3-D3)") (class "Default")
      (node (ref "P3") (pin "10") (pinfunction "D3_10") (pintype "passive"))
      (node (ref "R27") (pin "1") (pinfunction "1_1") (pintype "passive"))
      (node (ref "R41") (pin "2") (pinfunction "2_2") (pintype "passive"))
    )
    (net (code "58") (name "Net-(P3-D4)") (class "Default")
      (node (ref "P3") (pin "11") (pinfunction "D4_11") (pintype "passive"))
      (node (ref "R26") (pin "1") (pinfunction "1_1") (pintype "passive"))
      (node (ref "R40") (pin "2") (pinfunction "2_2") (pintype "passive"))
    )
    (net (code "59") (name "Net-(P3-D5)") (class "Default")
      (node (ref "P3") (pin "12") (pinfunction "D5_12") (pintype "passive"))
      (node (ref "R25") (pin "1") (pinfunction "1_1") (pintype "passive"))
      (node (ref "R39") (pin "2") (pinfunction "2_2") (pintype "passive"))
    )
    (net (code "60") (name "Net-(P3-D6)") (class "Default")
      (node (ref "P3") (pin "13") (pinfunction "D6_13") (pintype "passive"))
      (node (ref "R24") (pin "1") (pinfunction "1_1") (pintype "passive"))
      (node (ref "R38") (pin "2") (pinfunction "2_2") (pintype "passive"))
    )
    (net (code "61") (name "Net-(P3-D7)") (class "Default")
      (node (ref "P3") (pin "14") (pinfunction "D7_14") (pintype "passive"))
      (node (ref "R23") (pin "1") (pinfunction "1_1") (pintype "passive"))
      (node (ref "R37") (pin "2") (pinfunction "2_2") (pintype "passive"))
    )
    (net (code "62") (name "Net-(P3-E)") (class "Default")
      (node (ref "P3") (pin "6") (pinfunction "E_6") (pintype "passive"))
      (node (ref "R34") (pin "1") (pinfunction "1_1") (pintype "passive"))
      (node (ref "R45") (pin "2") (pinfunction "2_2") (pintype "passive"))
    )
    (net (code "63") (name "Net-(P3-RS)") (class "Default")
      (node (ref "P3") (pin "4") (pinfunction "RS_4") (pintype "passive"))
      (node (ref "R36") (pin "1") (pinfunction "1_1") (pintype "passive"))
      (node (ref "R47") (pin "2") (pinfunction "2_2") (pintype "passive"))
    )
    (net (code "64") (name "Net-(P3-RW)") (class "Default")
      (node (ref "P3") (pin "5") (pinfunction "RW_5") (pintype "passive"))
      (node (ref "R35") (pin "1") (pinfunction "1_1") (pintype "passive"))
      (node (ref "R46") (pin "2") (pinfunction "2_2") (pintype "passive"))
    )
    (net (code "65") (name "Net-(P3-V0)") (class "Default")
      (node (ref "P3") (pin "3") (pinfunction "V0_3") (pintype "passive"))
      (node (ref "VR1") (pin "2") (pinfunction "WIPER_2") (pintype "passive"))
    )
    (net (code "66") (name "Net-(Q1-B)") (class "Default")
      (node (ref "Q1") (pin "1") (pinfunction "B_1") (pintype "passive"))
      (node (ref "R7") (pin "2") (pinfunction "2_2") (pintype "passive"))
    )
    (net (code "67") (name "Net-(Q1-E)") (class "Default")
      (node (ref "Q1") (pin "2") (pinfunction "E_2") (pintype "passive"))
      (node (ref "R9") (pin "2") (pinfunction "2_2") (pintype "passive"))
      (node (ref "U2") (pin "14") (pinfunction "RTS#_14") (pintype "passive"))
    )
    (net (code "68") (name "Net-(Q2-B)") (class "Default")
      (node (ref "Q2") (pin "1") (pinfunction "B_1") (pintype "passive"))
      (node (ref "R9") (pin "1") (pinfunction "1_1") (pintype "passive"))
    )
    (net (code "69") (name "Net-(Q2-C)") (class "Default")
      (node (ref "Q2") (pin "3") (pinfunction "C_3") (pintype "passive"))
      (node (ref "R10") (pin "2") (pinfunction "2_2") (pintype "passive"))
    )
    (net (code "70") (name "Net-(Q3-B)") (class "Default")
      (node (ref "Q3") (pin "1") (pinfunction "B_1") (pintype "passive"))
      (node (ref "R15") (pin "1") (pinfunction "1_1") (pintype "passive"))
      (node (ref "R16") (pin "2") (pinfunction "2_2") (pintype "passive"))
    )
    (net (code "71") (name "Net-(Q4-B)") (class "Default")
      (node (ref "Q4") (pin "1") (pinfunction "B_1") (pintype "passive"))
      (node (ref "R29") (pin "1") (pinfunction "1_1") (pintype "passive"))
    )
    (net (code "72") (name "Net-(Q4-C)") (class "Default")
      (node (ref "Q4") (pin "3") (pinfunction "C_3") (pintype "passive"))
      (node (ref "R21") (pin "1") (pinfunction "1_1") (pintype "passive"))
      (node (ref "R22") (pin "2") (pinfunction "2_2") (pintype "passive"))
    )
    (net (code "73") (name "Net-(U2-DTR#)") (class "Default")
      (node (ref "R7") (pin "1") (pinfunction "1_1") (pintype "passive"))
      (node (ref "U2") (pin "13") (pinfunction "DTR#_13") (pintype "passive"))
    )
    (net (code "74") (name "Net-(U2-V3)") (class "Default")
      (node (ref "C11") (pin "2") (pinfunction "2_2") (pintype "passive"))
      (node (ref "U2") (pin "4") (pinfunction "V3_4") (pintype "power_in"))
    )
    (net (code "75") (name "Net-(U2-XI)") (class "Default")
      (node (ref "C13") (pin "1") (pinfunction "1_1") (pintype "passive"))
      (node (ref "U2") (pin "7") (pinfunction "XI_7") (pintype "passive"))
      (node (ref "Y2") (pin "1") (pinfunction "OSC1_1") (pintype "passive"))
    )
    (net (code "76") (name "Net-(U2-XO)") (class "Default")
      (node (ref "C15") (pin "1") (pinfunction "1_1") (pintype "passive"))
      (node (ref "U2") (pin "8") (pinfunction "XO_8") (pintype "passive"))
      (node (ref "Y2") (pin "2") (pinfunction "OSC2_2") (pintype "passive"))
    )
    (net (code "77") (name "unconnected-(IC1-N.C.-Pad8)") (class "Default")
      (node (ref "IC1") (pin "8") (pinfunction "N.C._8") (pintype "passive+no_connect"))
    )
    (net (code "78") (name "unconnected-(J1-ID-Pad4)") (class "Default")
      (node (ref "J1") (pin "4") (pinfunction "ID_4") (pintype "passive+no_connect"))
    )
    (net (code "79") (name "unconnected-(S2-COM_2-PadB1)") (class "Default")
      (node (ref "S2") (pin "B1") (pinfunction "COM_2_B1") (pintype "passive"))
    )
    (net (code "80") (name "unconnected-(S2-NO_2-PadD1)") (class "Default")
      (node (ref "S2") (pin "D1") (pinfunction "NO_2_D1") (pintype "passive"))
    )
    (net (code "81") (name "unconnected-(S3-COM_1-PadA1)") (class "Default")
      (node (ref "S3") (pin "A1") (pinfunction "COM_1_A1") (pintype "passive"))
    )
    (net (code "82") (name "unconnected-(S3-NO_1-PadC1)") (class "Default")
      (node (ref "S3") (pin "C1") (pinfunction "NO_1_C1") (pintype "passive"))
    )
    (net (code "83") (name "unconnected-(S4-COM_2-PadB1)") (class "Default")
      (node (ref "S4") (pin "B1") (pinfunction "COM_2_B1") (pintype "passive"))
    )
    (net (code "84") (name "unconnected-(S4-NO_2-PadD1)") (class "Default")
      (node (ref "S4") (pin "D1") (pinfunction "NO_2_D1") (pintype "passive"))
    )
    (net (code "85") (name "unconnected-(S5-COM_2-PadB1)") (class "Default")
      (node (ref "S5") (pin "B1") (pinfunction "COM_2_B1") (pintype "passive"))
    )
    (net (code "86") (name "unconnected-(S5-NO_2-PadD1)") (class "Default")
      (node (ref "S5") (pin "D1") (pinfunction "NO_2_D1") (pintype "passive"))
    )
    (net (code "87") (name "unconnected-(U1-NC-Pad4)") (class "Default")
      (node (ref "U1") (pin "4") (pinfunction "NC_4") (pintype "passive+no_connect"))
    )
    (net (code "88") (name "unconnected-(U2-CTS#-Pad9)") (class "Default")
      (node (ref "U2") (pin "9") (pinfunction "CTS#_9") (pintype "passive"))
    )
    (net (code "89") (name "unconnected-(U2-DCD#-Pad12)") (class "Default")
      (node (ref "U2") (pin "12") (pinfunction "DCD#_12") (pintype "passive"))
    )
    (net (code "90") (name "unconnected-(U2-DSR#-Pad10)") (class "Default")
      (node (ref "U2") (pin "10") (pinfunction "DSR#_10") (pintype "passive"))
    )
    (net (code "91") (name "unconnected-(U2-R232-Pad15)") (class "Default")
      (node (ref "U2") (pin "15") (pinfunction "R232_15") (pintype "passive"))
    )
    (net (code "92") (name "unconnected-(U2-RI#-Pad11)") (class "Default")
      (node (ref "U2") (pin "11") (pinfunction "RI#_11") (pintype "passive"))
    )
    (net (code "93") (name "unconnected-(U3-PA7-Pad17)") (class "Default")
      (node (ref "U3") (pin "17") (pinfunction "PA7_17") (pintype "passive+no_connect"))
    )
    (net (code "94") (name "unconnected-(U3-PA15-Pad38)") (class "Default")
      (node (ref "U3") (pin "38") (pinfunction "PA15_38") (pintype "passive+no_connect"))
    )
    (net (code "95") (name "unconnected-(U3-PB9-Pad46)") (class "Default")
      (node (ref "U3") (pin "46") (pinfunction "PB9_46") (pintype "passive+no_connect"))
    )
    (net (code "96") (name "unconnected-(U3-PB13-Pad26)") (class "Default")
      (node (ref "U3") (pin "26") (pinfunction "PB13_26") (pintype "passive+no_connect"))
    )
    (net (code "97") (name "unconnected-(U3-PB14-Pad27)") (class "Default")
      (node (ref "U3") (pin "27") (pinfunction "PB14_27") (pintype "passive+no_connect"))
    )
    (net (code "98") (name "unconnected-(U3-PB15-Pad28)") (class "Default")
      (node (ref "U3") (pin "28") (pinfunction "PB15_28") (pintype "passive+no_connect"))
    )
    (net (code "99") (name "unconnected-(U3-PC13-Pad2)") (class "Default")
      (node (ref "U3") (pin "2") (pinfunction "PC13_2") (pintype "passive+no_connect"))
    )
    (net (code "100") (name "unconnected-(U3-PC14{slash}OSC32_IN-Pad3)") (class "Default")
      (node (ref "U3") (pin "3") (pinfunction "PC14/OSC32_IN_3") (pintype "passive+no_connect"))
    )
    (net (code "101") (name "unconnected-(U3-PC15{slash}OSC32_OUT-Pad4)") (class "Default")
      (node (ref "U3") (pin "4") (pinfunction "PC15/OSC32_OUT_4") (pintype "passive+no_connect"))
    )
  )
)
